# RGB_SCHEMATIC.net
KiCad netlist of a schematic drawn in Altium Designer
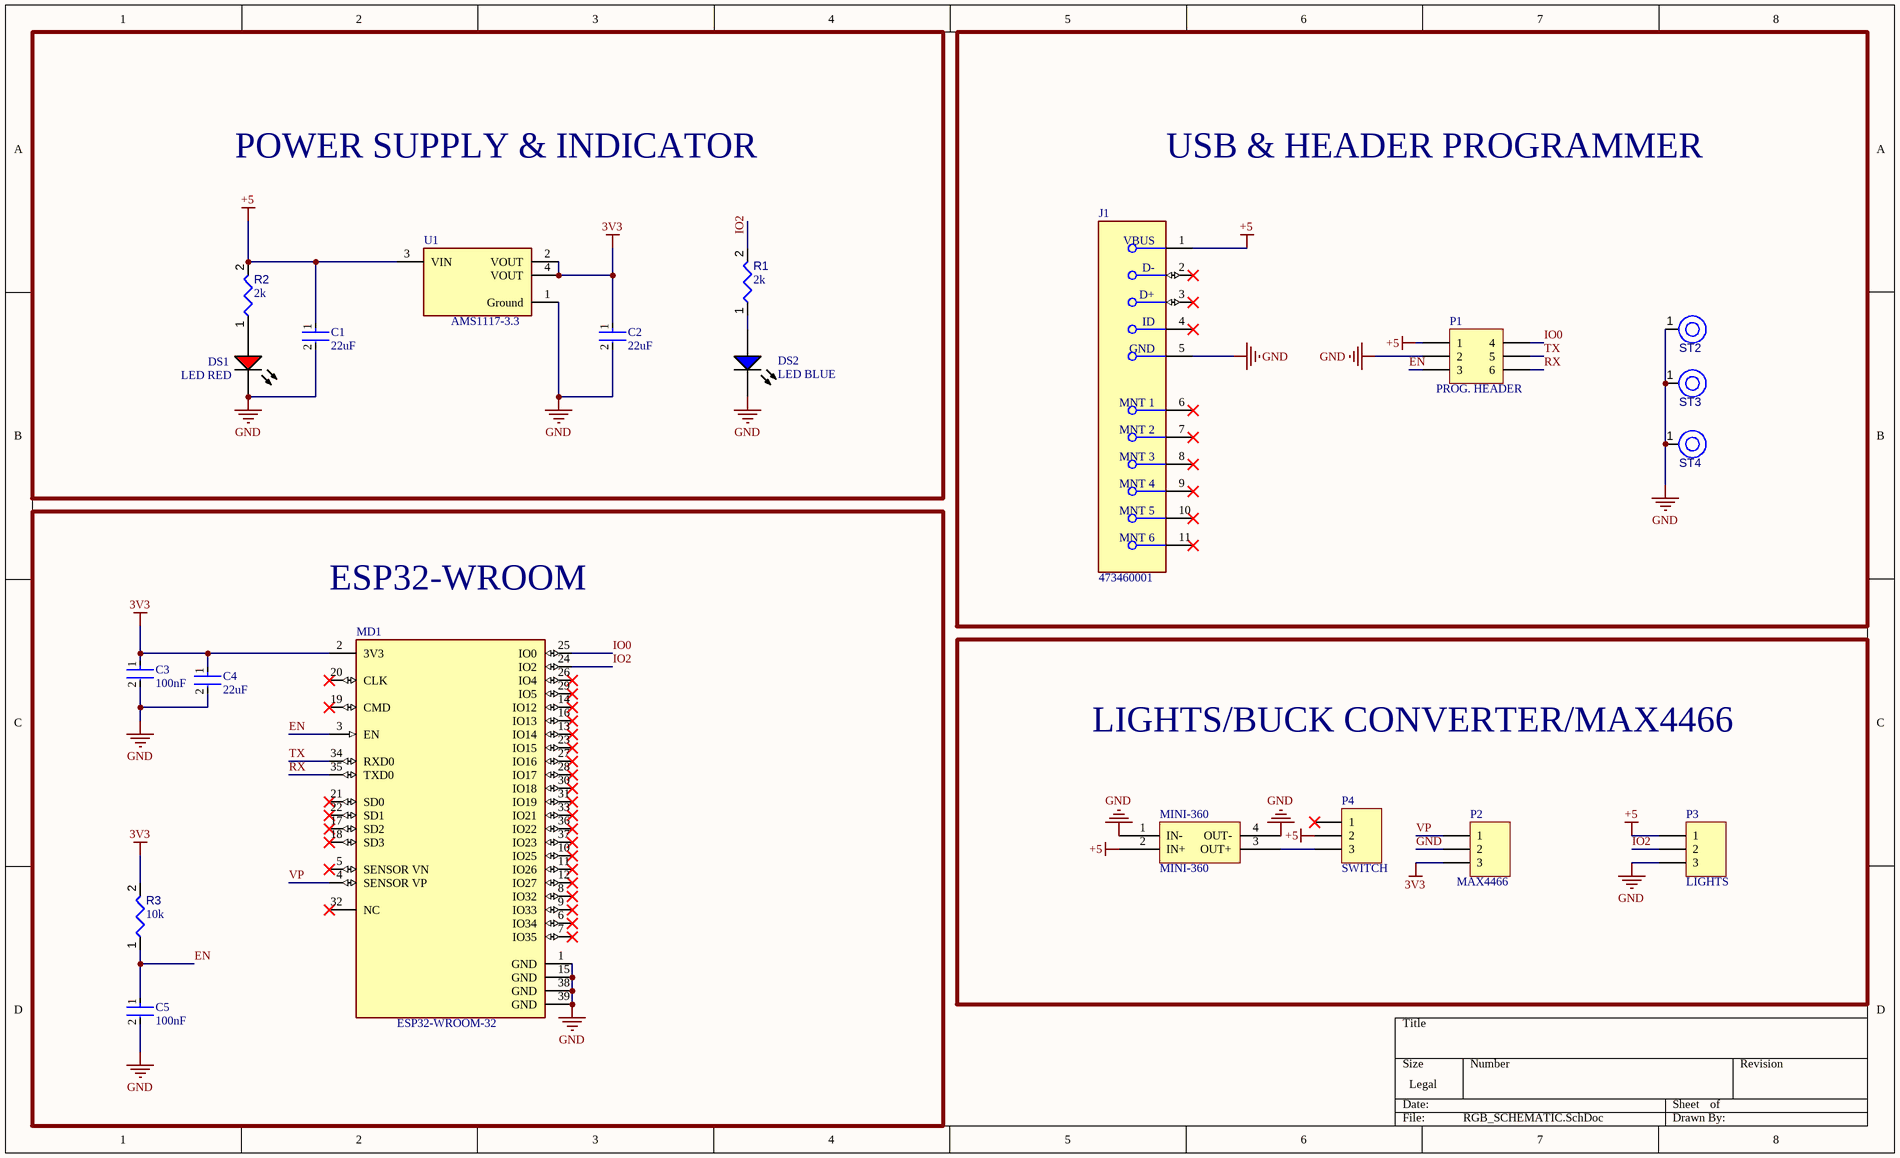
[diagram p0: RGB_SCHEMATIC.SchDoc]

(export (version "E")
  (design (tool "Eeschema 10.0.6"))
  (components
    (comp (ref "C1")
      (value "22uF")
      (footprint "FP-1206-L_3_2_0_2-W_1_6_0-IPC_C")
      (description "General Purpose Ceramic Capacitor, 1206, 22uF, 10%, X5R, 15%, 16V")
      (fields (field (name "TOLERANCE") "10%"))
      (libsource (lib "Altium Content Vault") (part "02cd4be3c70576c341d710602a673aa"))
    )
    (comp (ref "C2")
      (value "22uF")
      (footprint "FP-1206-L_3_2_0_2-W_1_6_0-IPC_C")
      (description "General Purpose Ceramic Capacitor, 1206, 22uF, 10%, X5R, 15%, 16V")
      (fields (field (name "TOLERANCE") "10%"))
      (libsource (lib "Altium Content Vault") (part "02cd4be3c70576c341d710602a673aa"))
    )
    (comp (ref "C3")
      (value "100nF")
      (footprint "FP-1206-L_3_2_0_2-W_1_6_0-MFG")
      (description "General Purpose Ceramic Capacitor, 1206, 100nF, 10%, X7R, 15%, 50V")
      (fields (field (name "TOLERANCE") "10%") (field (name "VOLTAGE") "50V"))
      (libsource (lib "Altium Content Vault") (part "02cd4be3c70576c341d710602a673aa"))
    )
    (comp (ref "C4")
      (value "22uF")
      (footprint "FP-1206-L_3_2_0_2-W_1_6_0-IPC_C")
      (description "General Purpose Ceramic Capacitor, 1206, 22uF, 10%, X5R, 15%, 16V")
      (fields (field (name "TOLERANCE") "10%"))
      (libsource (lib "Altium Content Vault") (part "02cd4be3c70576c341d710602a673aa"))
    )
    (comp (ref "C5")
      (value "100nF")
      (footprint "FP-1206-L_3_2_0_2-W_1_6_0-MFG")
      (description "General Purpose Ceramic Capacitor, 1206, 100nF, 10%, X7R, 15%, 50V")
      (fields (field (name "TOLERANCE") "10%") (field (name "VOLTAGE") "50V"))
      (libsource (lib "Altium Content Vault") (part "02cd4be3c70576c341d710602a673aa"))
    )
    (comp (ref "DS1")
      (value "LED RED")
      (footprint "LTST-C191KRKT_V")
      (description "LED Uni-Color Red, 62.5 mW, 25 mA, -30 to 85 degC, 2-Pin SMD, RoHS, Tape and Reel")
      (fields (field (name "POWER") "75mW") (field (name "MANUFACTURER") "Lite-On"))
      (libsource (lib "Florida Atlantic University") (part "LED-RED-AK-2"))
    )
    (comp (ref "DS2")
      (value "LED BLUE")
      (footprint "VISH-TLMX1100-2_V")
      (description "Blue LED, 10 mA, 3.9 V, -40 to 100 degC, 2-Pin SMD (0603), RoHS, Tape and Reel")
      (fields (field (name "POWER") "68mW") (field (name "MANUFACTURER") "Vishay Semiconductor"))
      (libsource (lib "Florida Atlantic University") (part "LED-BLUE-AK-2"))
    )
    (comp (ref "J1")
      (value "473460001")
      (footprint "FP-473460001-MFG")
      (description "CONN RCPT USB2.0 MICRO B SMD R/A")
      (fields
        (field (name "OCTOPART") "https://octopart.com/47346-0001-molex-7164928")
        (field (name "MANUFACTURER") "Molex")
      )
      (libsource (lib "Altium Content Vault") (part "53ae1f1d9b557310b43ca686e5bb76a"))
    )
    (comp (ref "MD1")
      (value "ESP32-WROOM-32")
      (footprint "FP-ESP32-WROOM-32-MFG")
      (description "RX TXRX MOD WIFI SURFACE MOUNT")
      (libsource (lib "Altium Content Vault") (part "ee866abf0b6c51247b7f5cdebf2f250"))
    )
    (comp (ref "MINI-360")
      (value "MINI-360")
      (footprint "MINI-360")
      (libsource (lib "Florida Atlantic University") (part "MINI-360"))
    )
    (comp (ref "P1")
      (value "PROG. HEADER")
      (footprint "HDR2X3_CEN")
      (description "Header, 3-Pin, Dual row")
      (fields (field (name "PUBLISHER") "Altium Limited"))
      (libsource (lib "Miscellaneous Connectors") (part "Header 3X2A"))
    )
    (comp (ref "P2")
      (value "MAX4466")
      (footprint "HDR1X3")
      (description "Header, 3-Pin")
      (fields (field (name "PUBLISHER") "Altium Limited"))
      (libsource (lib "Miscellaneous Connectors") (part "Header 3"))
    )
    (comp (ref "P3")
      (value "LIGHTS")
      (footprint "HDR1X3")
      (description "Header, 3-Pin")
      (fields (field (name "PUBLISHER") "Altium Limited"))
      (libsource (lib "Miscellaneous Connectors") (part "Header 3"))
    )
    (comp (ref "P4")
      (value "SWITCH")
      (footprint "HDR1X3")
      (description "Header, 3-Pin")
      (fields (field (name "PUBLISHER") "Altium Limited"))
      (libsource (lib "Miscellaneous Connectors") (part "Header 3"))
    )
    (comp (ref "R1")
      (value "2k")
      (footprint "RESC0402(1005)_L")
      (description "Chip Resistor, 2 kOhms, +/-5 %, 63 mW, -55 to 155 degC, 0402")
      (fields (field (name "TOLERANCE") "5%") (field (name "POWER") "63mW"))
      (libsource (lib "Florida Atlantic University") (part "RES-2"))
    )
    (comp (ref "R2")
      (value "2k")
      (footprint "RESC0402(1005)_L")
      (description "Chip Resistor, 2 kOhms, +/-5 %, 63 mW, -55 to 155 degC, 0402")
      (fields (field (name "TOLERANCE") "5%") (field (name "POWER") "63mW"))
      (libsource (lib "Florida Atlantic University") (part "RES-2"))
    )
    (comp (ref "R3")
      (value "10k")
      (footprint "RESC1608X55X25ML10T15")
      (description "Chip Resistor, 10 KOhm, +/- 1%, 01 W, -55 to 155 degC, 0603 (1608 Metric)")
      (fields (field (name "POWER") "100mW") (field (name "TOLERANCE") "1%"))
      (libsource (lib "Florida Atlantic University") (part "RES-2"))
    )
    (comp (ref "ST2")
      (value "PTH-M2D5X5")
      (footprint "PTH-M2D5X5")
      (description "M2 PTH (2.5mm), 5mm pad")
      (libsource (lib "Florida Atlantic University") (part "CMP-00028-00000-1"))
    )
    (comp (ref "ST3")
      (value "PTH-M2D5X5")
      (footprint "PTH-M2D5X5")
      (description "M2 PTH (2.5mm), 5mm pad")
      (libsource (lib "Florida Atlantic University") (part "CMP-00028-00000-1"))
    )
    (comp (ref "ST4")
      (value "PTH-M2D5X5")
      (footprint "PTH-M2D5X5")
      (description "M2 PTH (2.5mm), 5mm pad")
      (libsource (lib "Florida Atlantic University") (part "CMP-00028-00000-1"))
    )
    (comp (ref "U1")
      (value "AMS1117-3.3")
      (footprint "FP-AMS1117-IPC_C")
      (description "LDO Voltage Regulators 1A, 3.3V")
      (fields
        (field (name "OCTOPART") "https://octopart.com/ams1117-3.3-advanced+monolithic+systems-25899300")
        (field (name "MANUFACTURER") "Advanced Monolithic Systems")
      )
      (libsource (lib "Altium Content Vault") (part "8bdbb5f8e77002000e30dd2845d0354"))
    )
  )
  (nets
    (net (code "1") (name "+5") (class "Default")
      (node (ref "C1") (pin "1") (pinfunction "1_1") (pintype "passive"))
      (node (ref "J1") (pin "1") (pinfunction "VBUS_1") (pintype "power_in"))
      (node (ref "MINI-360") (pin "2") (pinfunction "IN+_2") (pintype "passive"))
      (node (ref "P1") (pin "1") (pinfunction "1_1") (pintype "passive"))
      (node (ref "P3") (pin "1") (pinfunction "1_1") (pintype "passive"))
      (node (ref "P4") (pin "2") (pinfunction "2_2") (pintype "passive"))
      (node (ref "R2") (pin "2") (pinfunction "2_2") (pintype "passive"))
      (node (ref "U1") (pin "3") (pinfunction "VIN_3") (pintype "power_in"))
    )
    (net (code "2") (name "/EN") (class "Default")
      (node (ref "C5") (pin "1") (pinfunction "1_1") (pintype "passive"))
      (node (ref "MD1") (pin "3") (pinfunction "EN_3") (pintype "input"))
      (node (ref "P1") (pin "3") (pinfunction "3_3") (pintype "passive"))
      (node (ref "R3") (pin "1") (pinfunction "1_1") (pintype "passive"))
    )
    (net (code "3") (name "/IO0") (class "Default")
      (node (ref "MD1") (pin "25") (pinfunction "IO0_25") (pintype "bidirectional"))
      (node (ref "P1") (pin "4") (pinfunction "4_4") (pintype "passive"))
    )
    (net (code "4") (name "/IO2") (class "Default")
      (node (ref "MD1") (pin "24") (pinfunction "IO2_24") (pintype "bidirectional"))
      (node (ref "P3") (pin "2") (pinfunction "2_2") (pintype "passive"))
      (node (ref "R1") (pin "2") (pinfunction "2_2") (pintype "passive"))
    )
    (net (code "5") (name "/RX") (class "Default")
      (node (ref "MD1") (pin "35") (pinfunction "TXD0_35") (pintype "bidirectional"))
      (node (ref "P1") (pin "6") (pinfunction "6_6") (pintype "passive"))
    )
    (net (code "6") (name "/TX") (class "Default")
      (node (ref "MD1") (pin "34") (pinfunction "RXD0_34") (pintype "bidirectional"))
      (node (ref "P1") (pin "5") (pinfunction "5_5") (pintype "passive"))
    )
    (net (code "7") (name "/VP") (class "Default")
      (node (ref "MD1") (pin "4") (pinfunction "SENSOR_VP_4") (pintype "bidirectional"))
      (node (ref "P2") (pin "1") (pinfunction "1_1") (pintype "passive"))
    )
    (net (code "8") (name "3V3") (class "Default")
      (node (ref "C2") (pin "1") (pinfunction "1_1") (pintype "passive"))
      (node (ref "C3") (pin "1") (pinfunction "1_1") (pintype "passive"))
      (node (ref "C4") (pin "1") (pinfunction "1_1") (pintype "passive"))
      (node (ref "MD1") (pin "2") (pinfunction "3V3_2") (pintype "power_in"))
      (node (ref "P2") (pin "3") (pinfunction "3_3") (pintype "passive"))
      (node (ref "R3") (pin "2") (pinfunction "2_2") (pintype "passive"))
      (node (ref "U1") (pin "2") (pinfunction "VOUT_2") (pintype "passive"))
      (node (ref "U1") (pin "4") (pinfunction "VOUT_4") (pintype "passive"))
    )
    (net (code "9") (name "GND") (class "Default")
      (node (ref "C1") (pin "2") (pinfunction "2_2") (pintype "passive"))
      (node (ref "C2") (pin "2") (pinfunction "2_2") (pintype "passive"))
      (node (ref "C3") (pin "2") (pinfunction "2_2") (pintype "passive"))
      (node (ref "C4") (pin "2") (pinfunction "2_2") (pintype "passive"))
      (node (ref "C5") (pin "2") (pinfunction "2_2") (pintype "passive"))
      (node (ref "DS1") (pin "2") (pinfunction "K_2") (pintype "passive"))
      (node (ref "DS2") (pin "2") (pinfunction "K_2") (pintype "passive"))
      (node (ref "J1") (pin "5") (pinfunction "GND_5") (pintype "power_in"))
      (node (ref "MD1") (pin "1") (pinfunction "GND_1") (pintype "power_in"))
      (node (ref "MD1") (pin "15") (pinfunction "GND_15") (pintype "power_in"))
      (node (ref "MD1") (pin "38") (pinfunction "GND_38") (pintype "power_in"))
      (node (ref "MD1") (pin "39") (pinfunction "GND_39") (pintype "power_in"))
      (node (ref "MINI-360") (pin "1") (pinfunction "IN-_1") (pintype "power_in"))
      (node (ref "MINI-360") (pin "4") (pinfunction "OUT-_4") (pintype "power_in"))
      (node (ref "P1") (pin "2") (pinfunction "2_2") (pintype "passive"))
      (node (ref "P2") (pin "2") (pinfunction "2_2") (pintype "passive"))
      (node (ref "P3") (pin "3") (pinfunction "3_3") (pintype "passive"))
      (node (ref "ST2") (pin "1") (pinfunction "H1_1") (pintype "passive"))
      (node (ref "ST3") (pin "1") (pinfunction "H1_1") (pintype "passive"))
      (node (ref "ST4") (pin "1") (pinfunction "H1_1") (pintype "passive"))
      (node (ref "U1") (pin "1") (pinfunction "Ground_1") (pintype "power_in"))
    )
    (net (code "10") (name "Net-(DS1-A)") (class "Default")
      (node (ref "DS1") (pin "1") (pinfunction "A_1") (pintype "passive"))
      (node (ref "R2") (pin "1") (pinfunction "1_1") (pintype "passive"))
    )
    (net (code "11") (name "Net-(DS2-A)") (class "Default")
      (node (ref "DS2") (pin "1") (pinfunction "A_1") (pintype "passive"))
      (node (ref "R1") (pin "1") (pinfunction "1_1") (pintype "passive"))
    )
    (net (code "12") (name "Net-(MINI-360-OUT+)") (class "Default")
      (node (ref "MINI-360") (pin "3") (pinfunction "OUT+_3") (pintype "power_in"))
      (node (ref "P4") (pin "3") (pinfunction "3_3") (pintype "passive"))
    )
    (net (code "13") (name "unconnected-(J1-D+-Pad3)") (class "Default")
      (node (ref "J1") (pin "3") (pinfunction "D+_3") (pintype "bidirectional+no_connect"))
    )
    (net (code "14") (name "unconnected-(J1-D--Pad2)") (class "Default")
      (node (ref "J1") (pin "2") (pinfunction "D-_2") (pintype "bidirectional+no_connect"))
    )
    (net (code "15") (name "unconnected-(J1-ID-Pad4)") (class "Default")
      (node (ref "J1") (pin "4") (pinfunction "ID_4") (pintype "passive+no_connect"))
    )
    (net (code "16") (name "unconnected-(J1-MNT_1-Pad6)") (class "Default")
      (node (ref "J1") (pin "6") (pinfunction "MNT_1_6") (pintype "passive+no_connect"))
    )
    (net (code "17") (name "unconnected-(J1-MNT_2-Pad7)") (class "Default")
      (node (ref "J1") (pin "7") (pinfunction "MNT_2_7") (pintype "passive+no_connect"))
    )
    (net (code "18") (name "unconnected-(J1-MNT_3-Pad8)") (class "Default")
      (node (ref "J1") (pin "8") (pinfunction "MNT_3_8") (pintype "passive+no_connect"))
    )
    (net (code "19") (name "unconnected-(J1-MNT_4-Pad9)") (class "Default")
      (node (ref "J1") (pin "9") (pinfunction "MNT_4_9") (pintype "passive+no_connect"))
    )
    (net (code "20") (name "unconnected-(J1-MNT_5-Pad10)") (class "Default")
      (node (ref "J1") (pin "10") (pinfunction "MNT_5_10") (pintype "passive+no_connect"))
    )
    (net (code "21") (name "unconnected-(J1-MNT_6-Pad11)") (class "Default")
      (node (ref "J1") (pin "11") (pinfunction "MNT_6_11") (pintype "passive+no_connect"))
    )
    (net (code "22") (name "unconnected-(MD1-CLK-Pad20)") (class "Default")
      (node (ref "MD1") (pin "20") (pinfunction "CLK_20") (pintype "bidirectional+no_connect"))
    )
    (net (code "23") (name "unconnected-(MD1-CMD-Pad19)") (class "Default")
      (node (ref "MD1") (pin "19") (pinfunction "CMD_19") (pintype "bidirectional+no_connect"))
    )
    (net (code "24") (name "unconnected-(MD1-IO4-Pad26)") (class "Default")
      (node (ref "MD1") (pin "26") (pinfunction "IO4_26") (pintype "bidirectional+no_connect"))
    )
    (net (code "25") (name "unconnected-(MD1-IO5-Pad29)") (class "Default")
      (node (ref "MD1") (pin "29") (pinfunction "IO5_29") (pintype "bidirectional+no_connect"))
    )
    (net (code "26") (name "unconnected-(MD1-IO12-Pad14)") (class "Default")
      (node (ref "MD1") (pin "14") (pinfunction "IO12_14") (pintype "bidirectional+no_connect"))
    )
    (net (code "27") (name "unconnected-(MD1-IO13-Pad16)") (class "Default")
      (node (ref "MD1") (pin "16") (pinfunction "IO13_16") (pintype "bidirectional+no_connect"))
    )
    (net (code "28") (name "unconnected-(MD1-IO14-Pad13)") (class "Default")
      (node (ref "MD1") (pin "13") (pinfunction "IO14_13") (pintype "bidirectional+no_connect"))
    )
    (net (code "29") (name "unconnected-(MD1-IO15-Pad23)") (class "Default")
      (node (ref "MD1") (pin "23") (pinfunction "IO15_23") (pintype "bidirectional+no_connect"))
    )
    (net (code "30") (name "unconnected-(MD1-IO16-Pad27)") (class "Default")
      (node (ref "MD1") (pin "27") (pinfunction "IO16_27") (pintype "bidirectional+no_connect"))
    )
    (net (code "31") (name "unconnected-(MD1-IO17-Pad28)") (class "Default")
      (node (ref "MD1") (pin "28") (pinfunction "IO17_28") (pintype "bidirectional+no_connect"))
    )
    (net (code "32") (name "unconnected-(MD1-IO18-Pad30)") (class "Default")
      (node (ref "MD1") (pin "30") (pinfunction "IO18_30") (pintype "bidirectional+no_connect"))
    )
    (net (code "33") (name "unconnected-(MD1-IO19-Pad31)") (class "Default")
      (node (ref "MD1") (pin "31") (pinfunction "IO19_31") (pintype "bidirectional+no_connect"))
    )
    (net (code "34") (name "unconnected-(MD1-IO21-Pad33)") (class "Default")
      (node (ref "MD1") (pin "33") (pinfunction "IO21_33") (pintype "bidirectional+no_connect"))
    )
    (net (code "35") (name "unconnected-(MD1-IO22-Pad36)") (class "Default")
      (node (ref "MD1") (pin "36") (pinfunction "IO22_36") (pintype "bidirectional+no_connect"))
    )
    (net (code "36") (name "unconnected-(MD1-IO23-Pad37)") (class "Default")
      (node (ref "MD1") (pin "37") (pinfunction "IO23_37") (pintype "bidirectional+no_connect"))
    )
    (net (code "37") (name "unconnected-(MD1-IO25-Pad10)") (class "Default")
      (node (ref "MD1") (pin "10") (pinfunction "IO25_10") (pintype "bidirectional+no_connect"))
    )
    (net (code "38") (name "unconnected-(MD1-IO26-Pad11)") (class "Default")
      (node (ref "MD1") (pin "11") (pinfunction "IO26_11") (pintype "bidirectional+no_connect"))
    )
    (net (code "39") (name "unconnected-(MD1-IO27-Pad12)") (class "Default")
      (node (ref "MD1") (pin "12") (pinfunction "IO27_12") (pintype "bidirectional+no_connect"))
    )
    (net (code "40") (name "unconnected-(MD1-IO32-Pad8)") (class "Default")
      (node (ref "MD1") (pin "8") (pinfunction "IO32_8") (pintype "bidirectional+no_connect"))
    )
    (net (code "41") (name "unconnected-(MD1-IO33-Pad9)") (class "Default")
      (node (ref "MD1") (pin "9") (pinfunction "IO33_9") (pintype "bidirectional+no_connect"))
    )
    (net (code "42") (name "unconnected-(MD1-IO34-Pad6)") (class "Default")
      (node (ref "MD1") (pin "6") (pinfunction "IO34_6") (pintype "bidirectional+no_connect"))
    )
    (net (code "43") (name "unconnected-(MD1-IO35-Pad7)") (class "Default")
      (node (ref "MD1") (pin "7") (pinfunction "IO35_7") (pintype "bidirectional+no_connect"))
    )
    (net (code "44") (name "unconnected-(MD1-NC-Pad32)") (class "Default")
      (node (ref "MD1") (pin "32") (pinfunction "NC_32") (pintype "passive+no_connect"))
    )
    (net (code "45") (name "unconnected-(MD1-SD0-Pad21)") (class "Default")
      (node (ref "MD1") (pin "21") (pinfunction "SD0_21") (pintype "bidirectional+no_connect"))
    )
    (net (code "46") (name "unconnected-(MD1-SD1-Pad22)") (class "Default")
      (node (ref "MD1") (pin "22") (pinfunction "SD1_22") (pintype "bidirectional+no_connect"))
    )
    (net (code "47") (name "unconnected-(MD1-SD2-Pad17)") (class "Default")
      (node (ref "MD1") (pin "17") (pinfunction "SD2_17") (pintype "bidirectional+no_connect"))
    )
    (net (code "48") (name "unconnected-(MD1-SD3-Pad18)") (class "Default")
      (node (ref "MD1") (pin "18") (pinfunction "SD3_18") (pintype "bidirectional+no_connect"))
    )
    (net (code "49") (name "unconnected-(MD1-SENSOR_VN-Pad5)") (class "Default")
      (node (ref "MD1") (pin "5") (pinfunction "SENSOR_VN_5") (pintype "bidirectional+no_connect"))
    )
    (net (code "50") (name "unconnected-(P4-Pad1)") (class "Default")
      (node (ref "P4") (pin "1") (pinfunction "1_1") (pintype "passive+no_connect"))
    )
  )
)
